# MainDin.net
KiCad netlist of a schematic drawn in Altium Designer
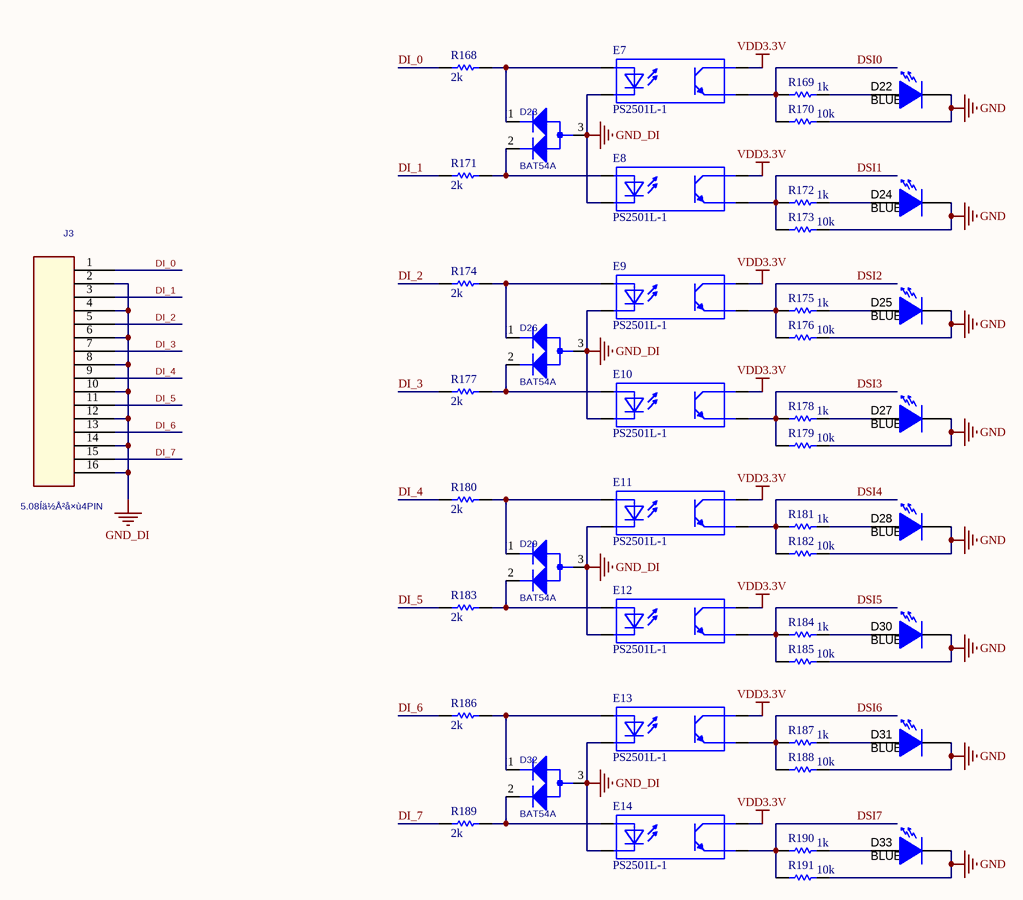
[diagram p0: MainDin.SchDoc]

(export (version "E")
  (design (tool "Eeschema 10.0.6"))
  (components
    (comp (ref "D22")
      (value "BLUE")
      (footprint "D0805")
      (description "LED, GREEN SMD")
      (fields
        (field (name "MANUFACTURER") "Rohm")
        (field (name "PARTNUMBER") "SML-P12YTT86")
        (field (name "PUBLISHER") "Texas Instruments")
      )
      (libsource (lib "REl") (part "SML-P12YTT86"))
    )
    (comp (ref "D23") (value "BAT54A") (footprint "SOT23") (libsource (lib "*") (part "BAT54A/SOT_2")))
    (comp (ref "D24")
      (value "BLUE")
      (footprint "D0805")
      (description "LED, GREEN SMD")
      (fields
        (field (name "MANUFACTURER") "Rohm")
        (field (name "PARTNUMBER") "SML-P12YTT86")
        (field (name "PUBLISHER") "Texas Instruments")
      )
      (libsource (lib "REl") (part "SML-P12YTT86"))
    )
    (comp (ref "D25")
      (value "BLUE")
      (footprint "D0805")
      (description "LED, GREEN SMD")
      (fields
        (field (name "MANUFACTURER") "Rohm")
        (field (name "PARTNUMBER") "SML-P12YTT86")
        (field (name "PUBLISHER") "Texas Instruments")
      )
      (libsource (lib "REl") (part "SML-P12YTT86"))
    )
    (comp (ref "D26") (value "BAT54A") (footprint "SOT23") (libsource (lib "*") (part "BAT54A/SOT_2")))
    (comp (ref "D27")
      (value "BLUE")
      (footprint "D0805")
      (description "LED, GREEN SMD")
      (fields
        (field (name "MANUFACTURER") "Rohm")
        (field (name "PARTNUMBER") "SML-P12YTT86")
        (field (name "PUBLISHER") "Texas Instruments")
      )
      (libsource (lib "REl") (part "SML-P12YTT86"))
    )
    (comp (ref "D28")
      (value "BLUE")
      (footprint "D0805")
      (description "LED, GREEN SMD")
      (fields
        (field (name "MANUFACTURER") "Rohm")
        (field (name "PARTNUMBER") "SML-P12YTT86")
        (field (name "PUBLISHER") "Texas Instruments")
      )
      (libsource (lib "REl") (part "SML-P12YTT86"))
    )
    (comp (ref "D29") (value "BAT54A") (footprint "SOT23") (libsource (lib "*") (part "BAT54A/SOT_2")))
    (comp (ref "D30")
      (value "BLUE")
      (footprint "D0805")
      (description "LED, GREEN SMD")
      (fields
        (field (name "MANUFACTURER") "Rohm")
        (field (name "PARTNUMBER") "SML-P12YTT86")
        (field (name "PUBLISHER") "Texas Instruments")
      )
      (libsource (lib "REl") (part "SML-P12YTT86"))
    )
    (comp (ref "D31")
      (value "BLUE")
      (footprint "D0805")
      (description "LED, GREEN SMD")
      (fields
        (field (name "MANUFACTURER") "Rohm")
        (field (name "PARTNUMBER") "SML-P12YTT86")
        (field (name "PUBLISHER") "Texas Instruments")
      )
      (libsource (lib "REl") (part "SML-P12YTT86"))
    )
    (comp (ref "D32") (value "BAT54A") (footprint "SOT23") (libsource (lib "*") (part "BAT54A/SOT_2")))
    (comp (ref "D33")
      (value "BLUE")
      (footprint "D0805")
      (description "LED, GREEN SMD")
      (fields
        (field (name "MANUFACTURER") "Rohm")
        (field (name "PARTNUMBER") "SML-P12YTT86")
        (field (name "PUBLISHER") "Texas Instruments")
      )
      (libsource (lib "REl") (part "SML-P12YTT86"))
    )
    (comp (ref "E7") (value "PS2501L-1") (description "光耦") (libsource (lib "*") (part "OPTO1")))
    (comp (ref "E8") (value "PS2501L-1") (description "光耦") (libsource (lib "*") (part "OPTO1")))
    (comp (ref "E9") (value "PS2501L-1") (description "光耦") (libsource (lib "*") (part "OPTO1")))
    (comp (ref "E10") (value "PS2501L-1") (description "光耦") (libsource (lib "*") (part "OPTO1")))
    (comp (ref "E11") (value "PS2501L-1") (description "光耦") (libsource (lib "*") (part "OPTO1")))
    (comp (ref "E12") (value "PS2501L-1") (description "光耦") (libsource (lib "*") (part "OPTO1")))
    (comp (ref "E13") (value "PS2501L-1") (description "光耦") (libsource (lib "*") (part "OPTO1")))
    (comp (ref "E14") (value "PS2501L-1") (description "光耦") (libsource (lib "*") (part "OPTO1")))
    (comp (ref "J3") (value "5.08弯脚插座4PIN") (footprint "JIEKE_16PX508") (libsource (lib "*") (part "CON16")))
    (comp (ref "R168")
      (value "2k")
      (footprint "0805")
      (description "Semiconductor Resistor")
      (fields (field (name "Comment") "Res Semi") (field (name "PUBLISHER") "Altium Limited"))
      (libsource (lib "Miscellaneous Devices") (part "Res Semi"))
    )
    (comp (ref "R169")
      (value "1k")
      (footprint "0805")
      (description "Semiconductor Resistor")
      (fields (field (name "Comment") "Res Semi") (field (name "PUBLISHER") "Altium Limited"))
      (libsource (lib "Miscellaneous Devices") (part "Res Semi"))
    )
    (comp (ref "R170")
      (value "10k")
      (footprint "0805")
      (description "Semiconductor Resistor")
      (fields (field (name "Comment") "Res Semi") (field (name "PUBLISHER") "Altium Limited"))
      (libsource (lib "Miscellaneous Devices") (part "Res Semi"))
    )
    (comp (ref "R171")
      (value "2k")
      (footprint "0805")
      (description "Semiconductor Resistor")
      (fields (field (name "Comment") "Res Semi") (field (name "PUBLISHER") "Altium Limited"))
      (libsource (lib "Miscellaneous Devices") (part "Res Semi"))
    )
    (comp (ref "R172")
      (value "1k")
      (footprint "0805")
      (description "Semiconductor Resistor")
      (fields (field (name "Comment") "Res Semi") (field (name "PUBLISHER") "Altium Limited"))
      (libsource (lib "Miscellaneous Devices") (part "Res Semi"))
    )
    (comp (ref "R173")
      (value "10k")
      (footprint "0805")
      (description "Semiconductor Resistor")
      (fields (field (name "Comment") "Res Semi") (field (name "PUBLISHER") "Altium Limited"))
      (libsource (lib "Miscellaneous Devices") (part "Res Semi"))
    )
    (comp (ref "R174")
      (value "2k")
      (footprint "0805")
      (description "Semiconductor Resistor")
      (fields (field (name "Comment") "Res Semi") (field (name "PUBLISHER") "Altium Limited"))
      (libsource (lib "Miscellaneous Devices") (part "Res Semi"))
    )
    (comp (ref "R175")
      (value "1k")
      (footprint "0805")
      (description "Semiconductor Resistor")
      (fields (field (name "Comment") "Res Semi") (field (name "PUBLISHER") "Altium Limited"))
      (libsource (lib "Miscellaneous Devices") (part "Res Semi"))
    )
    (comp (ref "R176")
      (value "10k")
      (footprint "0805")
      (description "Semiconductor Resistor")
      (fields (field (name "Comment") "Res Semi") (field (name "PUBLISHER") "Altium Limited"))
      (libsource (lib "Miscellaneous Devices") (part "Res Semi"))
    )
    (comp (ref "R177")
      (value "2k")
      (footprint "0805")
      (description "Semiconductor Resistor")
      (fields (field (name "Comment") "Res Semi") (field (name "PUBLISHER") "Altium Limited"))
      (libsource (lib "Miscellaneous Devices") (part "Res Semi"))
    )
    (comp (ref "R178")
      (value "1k")
      (footprint "0805")
      (description "Semiconductor Resistor")
      (fields (field (name "Comment") "Res Semi") (field (name "PUBLISHER") "Altium Limited"))
      (libsource (lib "Miscellaneous Devices") (part "Res Semi"))
    )
    (comp (ref "R179")
      (value "10k")
      (footprint "0805")
      (description "Semiconductor Resistor")
      (fields (field (name "Comment") "Res Semi") (field (name "PUBLISHER") "Altium Limited"))
      (libsource (lib "Miscellaneous Devices") (part "Res Semi"))
    )
    (comp (ref "R180")
      (value "2k")
      (footprint "0805")
      (description "Semiconductor Resistor")
      (fields (field (name "Comment") "Res Semi") (field (name "PUBLISHER") "Altium Limited"))
      (libsource (lib "Miscellaneous Devices") (part "Res Semi"))
    )
    (comp (ref "R181")
      (value "1k")
      (footprint "0805")
      (description "Semiconductor Resistor")
      (fields (field (name "Comment") "Res Semi") (field (name "PUBLISHER") "Altium Limited"))
      (libsource (lib "Miscellaneous Devices") (part "Res Semi"))
    )
    (comp (ref "R182")
      (value "10k")
      (footprint "0805")
      (description "Semiconductor Resistor")
      (fields (field (name "Comment") "Res Semi") (field (name "PUBLISHER") "Altium Limited"))
      (libsource (lib "Miscellaneous Devices") (part "Res Semi"))
    )
    (comp (ref "R183")
      (value "2k")
      (footprint "0805")
      (description "Semiconductor Resistor")
      (fields (field (name "Comment") "Res Semi") (field (name "PUBLISHER") "Altium Limited"))
      (libsource (lib "Miscellaneous Devices") (part "Res Semi"))
    )
    (comp (ref "R184")
      (value "1k")
      (footprint "0805")
      (description "Semiconductor Resistor")
      (fields (field (name "Comment") "Res Semi") (field (name "PUBLISHER") "Altium Limited"))
      (libsource (lib "Miscellaneous Devices") (part "Res Semi"))
    )
    (comp (ref "R185")
      (value "10k")
      (footprint "0805")
      (description "Semiconductor Resistor")
      (fields (field (name "Comment") "Res Semi") (field (name "PUBLISHER") "Altium Limited"))
      (libsource (lib "Miscellaneous Devices") (part "Res Semi"))
    )
    (comp (ref "R186")
      (value "2k")
      (footprint "0805")
      (description "Semiconductor Resistor")
      (fields (field (name "Comment") "Res Semi") (field (name "PUBLISHER") "Altium Limited"))
      (libsource (lib "Miscellaneous Devices") (part "Res Semi"))
    )
    (comp (ref "R187")
      (value "1k")
      (footprint "0805")
      (description "Semiconductor Resistor")
      (fields (field (name "Comment") "Res Semi") (field (name "PUBLISHER") "Altium Limited"))
      (libsource (lib "Miscellaneous Devices") (part "Res Semi"))
    )
    (comp (ref "R188")
      (value "10k")
      (footprint "0805")
      (description "Semiconductor Resistor")
      (fields (field (name "Comment") "Res Semi") (field (name "PUBLISHER") "Altium Limited"))
      (libsource (lib "Miscellaneous Devices") (part "Res Semi"))
    )
    (comp (ref "R189")
      (value "2k")
      (footprint "0805")
      (description "Semiconductor Resistor")
      (fields (field (name "Comment") "Res Semi") (field (name "PUBLISHER") "Altium Limited"))
      (libsource (lib "Miscellaneous Devices") (part "Res Semi"))
    )
    (comp (ref "R190")
      (value "1k")
      (footprint "0805")
      (description "Semiconductor Resistor")
      (fields (field (name "Comment") "Res Semi") (field (name "PUBLISHER") "Altium Limited"))
      (libsource (lib "Miscellaneous Devices") (part "Res Semi"))
    )
    (comp (ref "R191")
      (value "10k")
      (footprint "0805")
      (description "Semiconductor Resistor")
      (fields (field (name "Comment") "Res Semi") (field (name "PUBLISHER") "Altium Limited"))
      (libsource (lib "Miscellaneous Devices") (part "Res Semi"))
    )
  )
  (nets
    (net (code "1") (name "/DI_0") (class "Default")
      (node (ref "J3") (pin "1") (pinfunction "1_1") (pintype "passive"))
      (node (ref "R168") (pin "1") (pinfunction "1_1") (pintype "passive"))
    )
    (net (code "2") (name "/DI_1") (class "Default")
      (node (ref "J3") (pin "3") (pinfunction "3_3") (pintype "passive"))
      (node (ref "R171") (pin "1") (pinfunction "1_1") (pintype "passive"))
    )
    (net (code "3") (name "/DI_2") (class "Default")
      (node (ref "J3") (pin "5") (pinfunction "5_5") (pintype "passive"))
      (node (ref "R174") (pin "1") (pinfunction "1_1") (pintype "passive"))
    )
    (net (code "4") (name "/DI_3") (class "Default")
      (node (ref "J3") (pin "7") (pinfunction "7_7") (pintype "passive"))
      (node (ref "R177") (pin "1") (pinfunction "1_1") (pintype "passive"))
    )
    (net (code "5") (name "/DI_4") (class "Default")
      (node (ref "J3") (pin "9") (pinfunction "9_9") (pintype "passive"))
      (node (ref "R180") (pin "1") (pinfunction "1_1") (pintype "passive"))
    )
    (net (code "6") (name "/DI_5") (class "Default")
      (node (ref "J3") (pin "11") (pinfunction "11_11") (pintype "passive"))
      (node (ref "R183") (pin "1") (pinfunction "1_1") (pintype "passive"))
    )
    (net (code "7") (name "/DI_6") (class "Default")
      (node (ref "J3") (pin "13") (pinfunction "13_13") (pintype "passive"))
      (node (ref "R186") (pin "1") (pinfunction "1_1") (pintype "passive"))
    )
    (net (code "8") (name "/DI_7") (class "Default")
      (node (ref "J3") (pin "15") (pinfunction "15_15") (pintype "passive"))
      (node (ref "R189") (pin "1") (pinfunction "1_1") (pintype "passive"))
    )
    (net (code "9") (name "/DSI0") (class "Default")
      (node (ref "E7") (pin "3") (pintype "passive"))
      (node (ref "R169") (pin "1") (pinfunction "1_1") (pintype "passive"))
      (node (ref "R170") (pin "1") (pinfunction "1_1") (pintype "passive"))
    )
    (net (code "10") (name "/DSI1") (class "Default")
      (node (ref "E8") (pin "3") (pintype "passive"))
      (node (ref "R172") (pin "1") (pinfunction "1_1") (pintype "passive"))
      (node (ref "R173") (pin "1") (pinfunction "1_1") (pintype "passive"))
    )
    (net (code "11") (name "/DSI2") (class "Default")
      (node (ref "E9") (pin "3") (pintype "passive"))
      (node (ref "R175") (pin "1") (pinfunction "1_1") (pintype "passive"))
      (node (ref "R176") (pin "1") (pinfunction "1_1") (pintype "passive"))
    )
    (net (code "12") (name "/DSI3") (class "Default")
      (node (ref "E10") (pin "3") (pintype "passive"))
      (node (ref "R178") (pin "1") (pinfunction "1_1") (pintype "passive"))
      (node (ref "R179") (pin "1") (pinfunction "1_1") (pintype "passive"))
    )
    (net (code "13") (name "/DSI4") (class "Default")
      (node (ref "E11") (pin "3") (pintype "passive"))
      (node (ref "R181") (pin "1") (pinfunction "1_1") (pintype "passive"))
      (node (ref "R182") (pin "1") (pinfunction "1_1") (pintype "passive"))
    )
    (net (code "14") (name "/DSI5") (class "Default")
      (node (ref "E12") (pin "3") (pintype "passive"))
      (node (ref "R184") (pin "1") (pinfunction "1_1") (pintype "passive"))
      (node (ref "R185") (pin "1") (pinfunction "1_1") (pintype "passive"))
    )
    (net (code "15") (name "/DSI6") (class "Default")
      (node (ref "E13") (pin "3") (pintype "passive"))
      (node (ref "R187") (pin "1") (pinfunction "1_1") (pintype "passive"))
      (node (ref "R188") (pin "1") (pinfunction "1_1") (pintype "passive"))
    )
    (net (code "16") (name "/DSI7") (class "Default")
      (node (ref "E14") (pin "3") (pintype "passive"))
      (node (ref "R190") (pin "1") (pinfunction "1_1") (pintype "passive"))
      (node (ref "R191") (pin "1") (pinfunction "1_1") (pintype "passive"))
    )
    (net (code "17") (name "GND") (class "Default")
      (node (ref "D22") (pin "2") (pinfunction "K_2") (pintype "passive"))
      (node (ref "D24") (pin "2") (pinfunction "K_2") (pintype "passive"))
      (node (ref "D25") (pin "2") (pinfunction "K_2") (pintype "passive"))
      (node (ref "D27") (pin "2") (pinfunction "K_2") (pintype "passive"))
      (node (ref "D28") (pin "2") (pinfunction "K_2") (pintype "passive"))
      (node (ref "D30") (pin "2") (pinfunction "K_2") (pintype "passive"))
      (node (ref "D31") (pin "2") (pinfunction "K_2") (pintype "passive"))
      (node (ref "D33") (pin "2") (pinfunction "K_2") (pintype "passive"))
      (node (ref "R170") (pin "2") (pinfunction "2_2") (pintype "passive"))
      (node (ref "R173") (pin "2") (pinfunction "2_2") (pintype "passive"))
      (node (ref "R176") (pin "2") (pinfunction "2_2") (pintype "passive"))
      (node (ref "R179") (pin "2") (pinfunction "2_2") (pintype "passive"))
      (node (ref "R182") (pin "2") (pinfunction "2_2") (pintype "passive"))
      (node (ref "R185") (pin "2") (pinfunction "2_2") (pintype "passive"))
      (node (ref "R188") (pin "2") (pinfunction "2_2") (pintype "passive"))
      (node (ref "R191") (pin "2") (pinfunction "2_2") (pintype "passive"))
    )
    (net (code "18") (name "GND_DI") (class "Default")
      (node (ref "D23") (pin "3") (pinfunction "3_3") (pintype "passive"))
      (node (ref "D26") (pin "3") (pinfunction "3_3") (pintype "passive"))
      (node (ref "D29") (pin "3") (pinfunction "3_3") (pintype "passive"))
      (node (ref "D32") (pin "3") (pinfunction "3_3") (pintype "passive"))
      (node (ref "E10") (pin "2") (pintype "passive"))
      (node (ref "E11") (pin "2") (pintype "passive"))
      (node (ref "E12") (pin "2") (pintype "passive"))
      (node (ref "E13") (pin "2") (pintype "passive"))
      (node (ref "E14") (pin "2") (pintype "passive"))
      (node (ref "E7") (pin "2") (pintype "passive"))
      (node (ref "E8") (pin "2") (pintype "passive"))
      (node (ref "E9") (pin "2") (pintype "passive"))
      (node (ref "J3") (pin "10") (pinfunction "10_10") (pintype "passive"))
      (node (ref "J3") (pin "12") (pinfunction "12_12") (pintype "passive"))
      (node (ref "J3") (pin "14") (pinfunction "14_14") (pintype "passive"))
      (node (ref "J3") (pin "16") (pinfunction "16_16") (pintype "passive"))
      (node (ref "J3") (pin "2") (pinfunction "2_2") (pintype "passive"))
      (node (ref "J3") (pin "4") (pinfunction "4_4") (pintype "passive"))
      (node (ref "J3") (pin "6") (pinfunction "6_6") (pintype "passive"))
      (node (ref "J3") (pin "8") (pinfunction "8_8") (pintype "passive"))
    )
    (net (code "19") (name "Net-(D22-A)") (class "Default")
      (node (ref "D22") (pin "1") (pinfunction "A_1") (pintype "passive"))
      (node (ref "R169") (pin "2") (pinfunction "2_2") (pintype "passive"))
    )
    (net (code "20") (name "Net-(D23-Pad1)") (class "Default")
      (node (ref "D23") (pin "1") (pinfunction "1_1") (pintype "passive"))
      (node (ref "E7") (pin "1") (pintype "passive"))
      (node (ref "R168") (pin "2") (pinfunction "2_2") (pintype "passive"))
    )
    (net (code "21") (name "Net-(D23-Pad2)") (class "Default")
      (node (ref "D23") (pin "2") (pinfunction "2_2") (pintype "passive"))
      (node (ref "E8") (pin "1") (pintype "passive"))
      (node (ref "R171") (pin "2") (pinfunction "2_2") (pintype "passive"))
    )
    (net (code "22") (name "Net-(D24-A)") (class "Default")
      (node (ref "D24") (pin "1") (pinfunction "A_1") (pintype "passive"))
      (node (ref "R172") (pin "2") (pinfunction "2_2") (pintype "passive"))
    )
    (net (code "23") (name "Net-(D25-A)") (class "Default")
      (node (ref "D25") (pin "1") (pinfunction "A_1") (pintype "passive"))
      (node (ref "R175") (pin "2") (pinfunction "2_2") (pintype "passive"))
    )
    (net (code "24") (name "Net-(D26-Pad1)") (class "Default")
      (node (ref "D26") (pin "1") (pinfunction "1_1") (pintype "passive"))
      (node (ref "E9") (pin "1") (pintype "passive"))
      (node (ref "R174") (pin "2") (pinfunction "2_2") (pintype "passive"))
    )
    (net (code "25") (name "Net-(D26-Pad2)") (class "Default")
      (node (ref "D26") (pin "2") (pinfunction "2_2") (pintype "passive"))
      (node (ref "E10") (pin "1") (pintype "passive"))
      (node (ref "R177") (pin "2") (pinfunction "2_2") (pintype "passive"))
    )
    (net (code "26") (name "Net-(D27-A)") (class "Default")
      (node (ref "D27") (pin "1") (pinfunction "A_1") (pintype "passive"))
      (node (ref "R178") (pin "2") (pinfunction "2_2") (pintype "passive"))
    )
    (net (code "27") (name "Net-(D28-A)") (class "Default")
      (node (ref "D28") (pin "1") (pinfunction "A_1") (pintype "passive"))
      (node (ref "R181") (pin "2") (pinfunction "2_2") (pintype "passive"))
    )
    (net (code "28") (name "Net-(D29-Pad1)") (class "Default")
      (node (ref "D29") (pin "1") (pinfunction "1_1") (pintype "passive"))
      (node (ref "E11") (pin "1") (pintype "passive"))
      (node (ref "R180") (pin "2") (pinfunction "2_2") (pintype "passive"))
    )
    (net (code "29") (name "Net-(D29-Pad2)") (class "Default")
      (node (ref "D29") (pin "2") (pinfunction "2_2") (pintype "passive"))
      (node (ref "E12") (pin "1") (pintype "passive"))
      (node (ref "R183") (pin "2") (pinfunction "2_2") (pintype "passive"))
    )
    (net (code "30") (name "Net-(D30-A)") (class "Default")
      (node (ref "D30") (pin "1") (pinfunction "A_1") (pintype "passive"))
      (node (ref "R184") (pin "2") (pinfunction "2_2") (pintype "passive"))
    )
    (net (code "31") (name "Net-(D31-A)") (class "Default")
      (node (ref "D31") (pin "1") (pinfunction "A_1") (pintype "passive"))
      (node (ref "R187") (pin "2") (pinfunction "2_2") (pintype "passive"))
    )
    (net (code "32") (name "Net-(D32-Pad1)") (class "Default")
      (node (ref "D32") (pin "1") (pinfunction "1_1") (pintype "passive"))
      (node (ref "E13") (pin "1") (pintype "passive"))
      (node (ref "R186") (pin "2") (pinfunction "2_2") (pintype "passive"))
    )
    (net (code "33") (name "Net-(D32-Pad2)") (class "Default")
      (node (ref "D32") (pin "2") (pinfunction "2_2") (pintype "passive"))
      (node (ref "E14") (pin "1") (pintype "passive"))
      (node (ref "R189") (pin "2") (pinfunction "2_2") (pintype "passive"))
    )
    (net (code "34") (name "Net-(D33-A)") (class "Default")
      (node (ref "D33") (pin "1") (pinfunction "A_1") (pintype "passive"))
      (node (ref "R190") (pin "2") (pinfunction "2_2") (pintype "passive"))
    )
    (net (code "35") (name "VDD3.3V") (class "Default")
      (node (ref "E10") (pin "4") (pintype "passive"))
      (node (ref "E11") (pin "4") (pintype "passive"))
      (node (ref "E12") (pin "4") (pintype "passive"))
      (node (ref "E13") (pin "4") (pintype "passive"))
      (node (ref "E14") (pin "4") (pintype "passive"))
      (node (ref "E7") (pin "4") (pintype "passive"))
      (node (ref "E8") (pin "4") (pintype "passive"))
      (node (ref "E9") (pin "4") (pintype "passive"))
    )
  )
)
